# 4x_0603.net
KiCad netlist of a schematic drawn in EAGLE
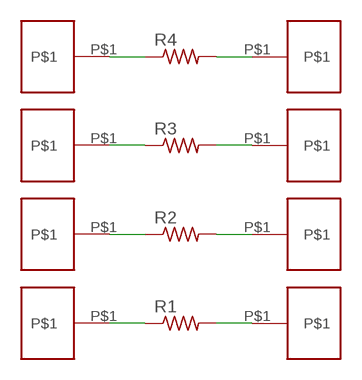
[diagram p0: schematic, sheet 1]

(export (version "E")
  (design (tool "Eeschema 10.0.6"))
  (components
    (comp (ref "R1")
      (value "R-US_R0603")
      (footprint "eagle-import:R0603")
      (libsource (lib "eagle-import") (part "R-US_R0603"))
    )
    (comp (ref "R2")
      (value "R-US_R0603")
      (footprint "eagle-import:R0603")
      (libsource (lib "eagle-import") (part "R-US_R0603"))
    )
    (comp (ref "R3")
      (value "R-US_R0603")
      (footprint "eagle-import:R0603")
      (libsource (lib "eagle-import") (part "R-US_R0603"))
    )
    (comp (ref "R4")
      (value "R-US_R0603")
      (footprint "eagle-import:R0603")
      (libsource (lib "eagle-import") (part "R-US_R0603"))
    )
    (comp (ref "U$1")
      (value "PAD100MIL")
      (footprint "eagle-import:100MIL_PAD")
      (libsource (lib "eagle-import") (part "PAD100MIL"))
    )
    (comp (ref "U$2")
      (value "PAD100MIL")
      (footprint "eagle-import:100MIL_PAD")
      (libsource (lib "eagle-import") (part "PAD100MIL"))
    )
    (comp (ref "U$3")
      (value "PAD100MIL")
      (footprint "eagle-import:100MIL_PAD")
      (libsource (lib "eagle-import") (part "PAD100MIL"))
    )
    (comp (ref "U$4")
      (value "PAD100MIL")
      (footprint "eagle-import:100MIL_PAD")
      (libsource (lib "eagle-import") (part "PAD100MIL"))
    )
    (comp (ref "U$5")
      (value "PAD100MIL")
      (footprint "eagle-import:100MIL_PAD")
      (libsource (lib "eagle-import") (part "PAD100MIL"))
    )
    (comp (ref "U$6")
      (value "PAD100MIL")
      (footprint "eagle-import:100MIL_PAD")
      (libsource (lib "eagle-import") (part "PAD100MIL"))
    )
    (comp (ref "U$7")
      (value "PAD100MIL")
      (footprint "eagle-import:100MIL_PAD")
      (libsource (lib "eagle-import") (part "PAD100MIL"))
    )
    (comp (ref "U$8")
      (value "PAD100MIL")
      (footprint "eagle-import:100MIL_PAD")
      (libsource (lib "eagle-import") (part "PAD100MIL"))
    )
  )
  (nets
    (net (code "1") (name "Net-(R1-Pad1)") (class "Default")
      (node (ref "R1") (pin "1") (pinfunction "1_1") (pintype "passive"))
      (node (ref "U$4") (pin "P$1") (pinfunction "P$1_P$1") (pintype "bidirectional"))
    )
    (net (code "2") (name "Net-(R1-Pad2)") (class "Default")
      (node (ref "R1") (pin "2") (pinfunction "2_2") (pintype "passive"))
      (node (ref "U$8") (pin "P$1") (pinfunction "P$1_P$1") (pintype "bidirectional"))
    )
    (net (code "3") (name "Net-(R2-Pad1)") (class "Default")
      (node (ref "R2") (pin "1") (pinfunction "1_1") (pintype "passive"))
      (node (ref "U$3") (pin "P$1") (pinfunction "P$1_P$1") (pintype "bidirectional"))
    )
    (net (code "4") (name "Net-(R2-Pad2)") (class "Default")
      (node (ref "R2") (pin "2") (pinfunction "2_2") (pintype "passive"))
      (node (ref "U$7") (pin "P$1") (pinfunction "P$1_P$1") (pintype "bidirectional"))
    )
    (net (code "5") (name "Net-(R3-Pad1)") (class "Default")
      (node (ref "R3") (pin "1") (pinfunction "1_1") (pintype "passive"))
      (node (ref "U$2") (pin "P$1") (pinfunction "P$1_P$1") (pintype "bidirectional"))
    )
    (net (code "6") (name "Net-(R3-Pad2)") (class "Default")
      (node (ref "R3") (pin "2") (pinfunction "2_2") (pintype "passive"))
      (node (ref "U$6") (pin "P$1") (pinfunction "P$1_P$1") (pintype "bidirectional"))
    )
    (net (code "7") (name "Net-(R4-Pad1)") (class "Default")
      (node (ref "R4") (pin "1") (pinfunction "1_1") (pintype "passive"))
      (node (ref "U$1") (pin "P$1") (pinfunction "P$1_P$1") (pintype "bidirectional"))
    )
    (net (code "8") (name "Net-(R4-Pad2)") (class "Default")
      (node (ref "R4") (pin "2") (pinfunction "2_2") (pintype "passive"))
      (node (ref "U$5") (pin "P$1") (pinfunction "P$1_P$1") (pintype "bidirectional"))
    )
  )
)
